# OZ440-SE100-CAR003_sheet16.net
KiCad netlist of a schematic drawn in Altium Designer
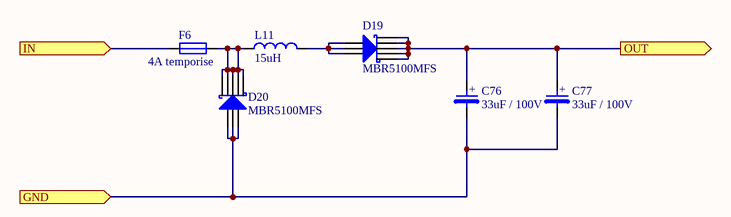
[diagram p0: OZ440-SE100-CAR003_sheet16.SchDoc]

(export (version "E")
  (design (tool "Eeschema 10.0.6"))
  (components
    (comp (ref "C76")
      (value "CAP-POL-SMD")
      (footprint "CAP-ELECTRO-SMD_SIZE_G")
      (description "33uF / 100V Aluminium capacitor SMD")
      (fields (field (name "DISPLAYED REFERENCE") "33uF / 100V") (field (name "MANUFACTURER") "Panasonic"))
      (libsource (lib "lib_NAIO") (part "CAP-POL-SMD"))
    )
    (comp (ref "C77")
      (value "CAP-POL-SMD")
      (footprint "CAP-ELECTRO-SMD_SIZE_G")
      (description "33uF / 100V Aluminium capacitor SMD")
      (fields (field (name "DISPLAYED REFERENCE") "33uF / 100V") (field (name "MANUFACTURER") "Panasonic"))
      (libsource (lib "lib_NAIO") (part "CAP-POL-SMD"))
    )
    (comp (ref "D19")
      (value "MBR5100MFS-SO8")
      (footprint "SO8-SPE-MBR5100MFS")
      (description "Power shottky Diode")
      (fields (field (name "DISPLAYED REFERENCE") "MBR5100MFS") (field (name "MANUFACTURER") "ON semi"))
      (libsource (lib "lib_NAIO") (part "MBR5100MFS-SO8"))
    )
    (comp (ref "D20")
      (value "MBR5100MFS-SO8")
      (footprint "SO8-SPE-MBR5100MFS")
      (description "Power shottky Diode")
      (fields (field (name "DISPLAYED REFERENCE") "MBR5100MFS") (field (name "MANUFACTURER") "ON semi"))
      (libsource (lib "lib_NAIO") (part "MBR5100MFS-SO8"))
    )
    (comp (ref "F6")
      (value "FUSE-SMD")
      (footprint "F1206-STD")
      (description "1206 4A 63V temporisé")
      (fields (field (name "DISPLAYED REFERENCE") "4A temporise") (field (name "MANUFACTURER") "MULTICOMP"))
      (libsource (lib "lib_NAIO") (part "FUSE-SMD"))
    )
    (comp (ref "L11")
      (value "IND-SMD")
      (footprint "L-SPE-XAL60xx")
      (description "15uH SMD inductor")
      (fields (field (name "DISPLAYED REFERENCE") "15uH") (field (name "MANUFACTURER") "COILCRAFT"))
      (libsource (lib "lib_NAIO") (part "IND-SMD"))
    )
  )
  (nets
    (net (code "1") (name "/GND") (class "Default")
      (node (ref "C76") (pin "2") (pinfunction "2_2") (pintype "passive"))
      (node (ref "C77") (pin "2") (pinfunction "2_2") (pintype "passive"))
      (node (ref "D20") (pin "1") (pinfunction "A_1") (pintype "passive"))
      (node (ref "D20") (pin "2") (pinfunction "A_2") (pintype "passive"))
      (node (ref "D20") (pin "3") (pinfunction "A_3") (pintype "passive"))
    )
    (net (code "2") (name "/IN") (class "Default")
      (node (ref "F6") (pin "1") (pinfunction "1_1") (pintype "passive"))
    )
    (net (code "3") (name "/OUT") (class "Default")
      (node (ref "C76") (pin "1") (pinfunction "1_1") (pintype "passive"))
      (node (ref "C77") (pin "1") (pinfunction "1_1") (pintype "passive"))
      (node (ref "D19") (pin "5") (pinfunction "K_5") (pintype "passive"))
      (node (ref "D19") (pin "6") (pinfunction "K_6") (pintype "passive"))
      (node (ref "D19") (pin "7") (pinfunction "K_7") (pintype "passive"))
      (node (ref "D19") (pin "8") (pinfunction "K_8") (pintype "passive"))
    )
    (net (code "4") (name "Net-(D19-A-Pad1)") (class "Default")
      (node (ref "D19") (pin "1") (pinfunction "A_1") (pintype "passive"))
      (node (ref "D19") (pin "2") (pinfunction "A_2") (pintype "passive"))
      (node (ref "D19") (pin "3") (pinfunction "A_3") (pintype "passive"))
      (node (ref "L11") (pin "2") (pinfunction "2_2") (pintype "passive"))
    )
    (net (code "5") (name "Net-(D20-K-Pad5)") (class "Default")
      (node (ref "D20") (pin "5") (pinfunction "K_5") (pintype "passive"))
      (node (ref "D20") (pin "6") (pinfunction "K_6") (pintype "passive"))
      (node (ref "D20") (pin "7") (pinfunction "K_7") (pintype "passive"))
      (node (ref "D20") (pin "8") (pinfunction "K_8") (pintype "passive"))
      (node (ref "F6") (pin "2") (pinfunction "2_2") (pintype "passive"))
      (node (ref "L11") (pin "1") (pinfunction "1_1") (pintype "passive"))
    )
  )
)
